# oled_control.net
KiCad netlist of a schematic drawn in Altium Designer
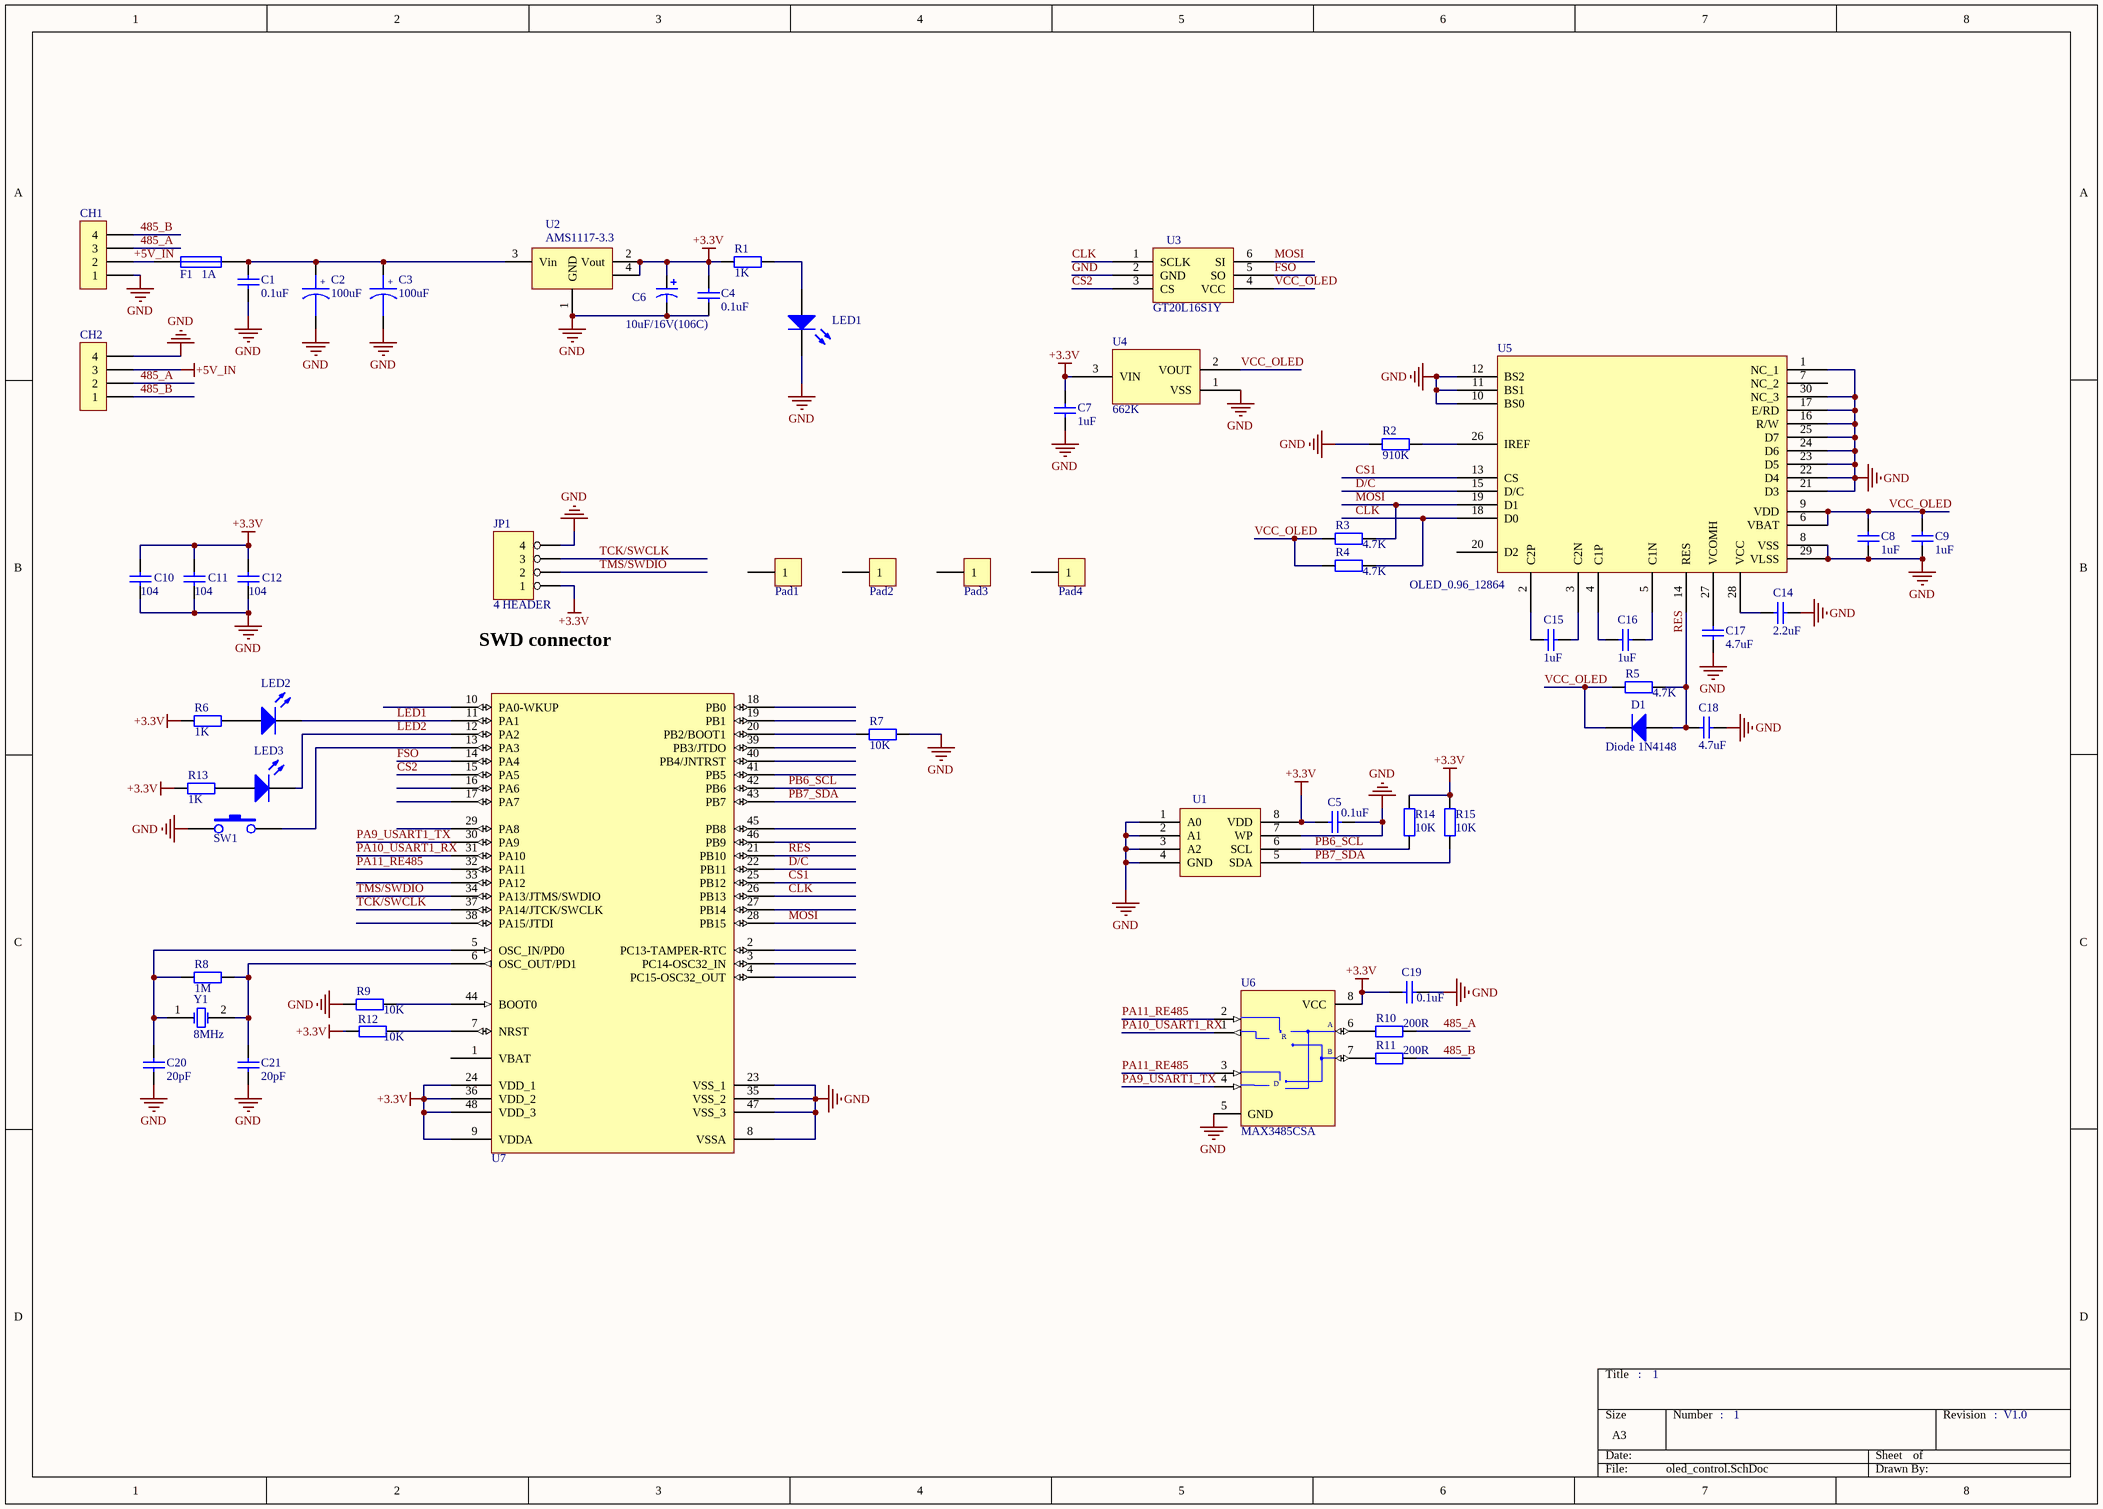
[diagram p0: oled_control.SchDoc]

(export (version "E")
  (design (tool "Eeschema 10.0.6"))
  (components
    (comp (ref "C1")
      (value "0.1uF")
      (footprint "0805")
      (description "Capacitor")
      (fields (field (name "Comment") "Cap") (field (name "PUBLISHER") "Altium Limited"))
      (libsource (lib "Miscellaneous Devices") (part "Cap"))
    )
    (comp (ref "C2")
      (value "C_2200uF")
      (footprint "B: 3528")
      (fields (field (name "ALTIUM_UNNAMED_1") "100uF"))
      (libsource (lib "myIntegrated_Library1") (part "C_2200uF"))
    )
    (comp (ref "C3")
      (value "C_2200uF")
      (footprint "B: 3528")
      (fields (field (name "ALTIUM_UNNAMED_1") "100uF"))
      (libsource (lib "myIntegrated_Library1") (part "C_2200uF"))
    )
    (comp (ref "C4")
      (value "0.1uF")
      (footprint "0805")
      (description "Capacitor")
      (fields (field (name "Comment") "Cap") (field (name "PUBLISHER") "Altium Limited"))
      (libsource (lib "Miscellaneous Devices") (part "Cap"))
    )
    (comp (ref "C5")
      (value "0.1uF")
      (footprint "0805")
      (description "Capacitor")
      (fields (field (name "Comment") "Cap") (field (name "PUBLISHER") "Altium Limited"))
      (libsource (lib "Miscellaneous Devices") (part "Cap"))
    )
    (comp (ref "C6")
      (value "10uF/16V(106C)")
      (footprint "CAP A-3216")
      (description "Polarized Capacitor (Surface Mount)")
      (fields (field (name "Comment") "Cap Pol3") (field (name "PUBLISHER") "Altium Limited"))
      (libsource (lib "Miscellaneous Devices") (part "Cap Pol3"))
    )
    (comp (ref "C7")
      (value "1uF")
      (footprint "0805")
      (description "Capacitor")
      (fields (field (name "Comment") "Cap") (field (name "PUBLISHER") "Altium Limited"))
      (libsource (lib "Miscellaneous Devices") (part "Cap"))
    )
    (comp (ref "C8")
      (value "1uF")
      (footprint "0805")
      (description "Capacitor")
      (fields (field (name "Comment") "Cap") (field (name "PUBLISHER") "Altium Limited"))
      (libsource (lib "Miscellaneous Devices") (part "Cap"))
    )
    (comp (ref "C9")
      (value "1uF")
      (footprint "0805")
      (description "Capacitor")
      (fields (field (name "Comment") "Cap") (field (name "PUBLISHER") "Altium Limited"))
      (libsource (lib "Miscellaneous Devices") (part "Cap"))
    )
    (comp (ref "C10")
      (value "104")
      (footprint "0805")
      (description "Capacitor")
      (fields (field (name "Comment") "Cap") (field (name "PUBLISHER") "Altium Limited"))
      (libsource (lib "Miscellaneous Devices") (part "Cap"))
    )
    (comp (ref "C11")
      (value "104")
      (footprint "0805")
      (description "Capacitor")
      (fields (field (name "Comment") "Cap") (field (name "PUBLISHER") "Altium Limited"))
      (libsource (lib "Miscellaneous Devices") (part "Cap"))
    )
    (comp (ref "C12")
      (value "104")
      (footprint "0805")
      (description "Capacitor")
      (fields (field (name "Comment") "Cap") (field (name "PUBLISHER") "Altium Limited"))
      (libsource (lib "Miscellaneous Devices") (part "Cap"))
    )
    (comp (ref "C14")
      (value "2.2uF")
      (footprint "0805")
      (description "Capacitor")
      (fields (field (name "Comment") "Cap") (field (name "PUBLISHER") "Altium Limited"))
      (libsource (lib "Miscellaneous Devices") (part "Cap"))
    )
    (comp (ref "C15")
      (value "1uF")
      (footprint "0805")
      (description "Capacitor")
      (fields (field (name "Comment") "Cap") (field (name "PUBLISHER") "Altium Limited"))
      (libsource (lib "Miscellaneous Devices") (part "Cap"))
    )
    (comp (ref "C16")
      (value "1uF")
      (footprint "0805")
      (description "Capacitor")
      (fields (field (name "Comment") "Cap") (field (name "PUBLISHER") "Altium Limited"))
      (libsource (lib "Miscellaneous Devices") (part "Cap"))
    )
    (comp (ref "C17")
      (value "4.7uF")
      (footprint "0805")
      (description "Capacitor")
      (fields (field (name "Comment") "Cap") (field (name "PUBLISHER") "Altium Limited"))
      (libsource (lib "Miscellaneous Devices") (part "Cap"))
    )
    (comp (ref "C18")
      (value "4.7uF")
      (footprint "0805")
      (description "Capacitor")
      (fields (field (name "Comment") "Cap") (field (name "PUBLISHER") "Altium Limited"))
      (libsource (lib "Miscellaneous Devices") (part "Cap"))
    )
    (comp (ref "C19")
      (value "0.1uF")
      (footprint "0805")
      (description "Capacitor")
      (fields (field (name "Comment") "Cap") (field (name "PUBLISHER") "Altium Limited"))
      (libsource (lib "Miscellaneous Devices") (part "Cap"))
    )
    (comp (ref "C20")
      (value "20pF")
      (footprint "0805")
      (description "Capacitor")
      (fields (field (name "Comment") "Cap") (field (name "PUBLISHER") "Altium Limited"))
      (libsource (lib "开发板元件库") (part "Cap"))
    )
    (comp (ref "C21")
      (value "20pF")
      (footprint "0805")
      (description "Capacitor")
      (fields (field (name "Comment") "Cap") (field (name "PUBLISHER") "Altium Limited"))
      (libsource (lib "开发板元件库") (part "Cap"))
    )
    (comp (ref "CH1")
      (value "HEADER1X4")
      (footprint "CON4_1.5")
      (libsource (lib "myIntegrated_Library1") (part "HEADER1X4"))
    )
    (comp (ref "CH2")
      (value "HEADER1X4")
      (footprint "CON4_1.5")
      (libsource (lib "myIntegrated_Library1") (part "HEADER1X4"))
    )
    (comp (ref "D1")
      (value "Diode 1N4148")
      (footprint "LL34")
      (description "High Conductance Fast Diode")
      (fields (field (name "PUBLISHER") "Altium Limited"))
      (libsource (lib "Miscellaneous Devices") (part "Diode 1N4148"))
    )
    (comp (ref "F1")
      (value "FUSE")
      (footprint "0805")
      (fields (field (name "ALTIUM_UNNAMED_1") "1A"))
      (libsource (lib "myIntegrated_Library1") (part "FUSE"))
    )
    (comp (ref "JP1")
      (value "4 HEADER")
      (footprint "CON4_1.5")
      (description "4 Pin Header")
      (libsource (lib "Miscellaneous Devices") (part "4 HEADER"))
    )
    (comp (ref "LED1")
      (value "~")
      (footprint "LED-0805")
      (description "Typical RED, GREEN, YELLOW, AMBER GaAs LED")
      (fields (field (name "PUBLISHER") "Altium Limited"))
      (libsource (lib "Miscellaneous Devices") (part "LED2"))
    )
    (comp (ref "LED2")
      (value "~")
      (footprint "LED-0805")
      (description "Typical RED, GREEN, YELLOW, AMBER GaAs LED")
      (fields (field (name "PUBLISHER") "Altium Limited"))
      (libsource (lib "Miscellaneous Devices") (part "LED2"))
    )
    (comp (ref "LED3")
      (value "~")
      (footprint "LED_5X5")
      (description "Typical RED, GREEN, YELLOW, AMBER GaAs LED")
      (fields (field (name "PUBLISHER") "Altium Limited"))
      (libsource (lib "Miscellaneous Devices") (part "LED2"))
    )
    (comp (ref "Pad1")
      (value "Pad")
      (footprint "pad35")
      (libsource (lib "myIntegrated_Library1") (part "Pad"))
    )
    (comp (ref "Pad2")
      (value "Pad")
      (footprint "pad35")
      (libsource (lib "myIntegrated_Library1") (part "Pad"))
    )
    (comp (ref "Pad3")
      (value "Pad")
      (footprint "pad35")
      (libsource (lib "myIntegrated_Library1") (part "Pad"))
    )
    (comp (ref "Pad4")
      (value "Pad")
      (footprint "pad35")
      (libsource (lib "myIntegrated_Library1") (part "Pad"))
    )
    (comp (ref "R1")
      (value "1K")
      (footprint "0805")
      (description "Resistor")
      (fields (field (name "Comment") "Res2") (field (name "PUBLISHER") "Altium Limited"))
      (libsource (lib "Miscellaneous Devices") (part "Res2"))
    )
    (comp (ref "R2")
      (value "910K")
      (footprint "0805")
      (description "Resistor")
      (fields (field (name "Comment") "Res2") (field (name "PUBLISHER") "Altium Limited"))
      (libsource (lib "Miscellaneous Devices") (part "Res2"))
    )
    (comp (ref "R3")
      (value "4.7K")
      (footprint "0805")
      (description "Resistor")
      (fields (field (name "Comment") "Res2") (field (name "PUBLISHER") "Altium Limited"))
      (libsource (lib "Miscellaneous Devices") (part "Res2"))
    )
    (comp (ref "R4")
      (value "4.7K")
      (footprint "0805")
      (description "Resistor")
      (fields (field (name "Comment") "Res2") (field (name "PUBLISHER") "Altium Limited"))
      (libsource (lib "Miscellaneous Devices") (part "Res2"))
    )
    (comp (ref "R5")
      (value "4.7K")
      (footprint "0805")
      (description "Resistor")
      (fields (field (name "Comment") "Res2") (field (name "PUBLISHER") "Altium Limited"))
      (libsource (lib "Miscellaneous Devices") (part "Res2"))
    )
    (comp (ref "R6")
      (value "1K")
      (footprint "0805")
      (description "Resistor")
      (fields (field (name "Comment") "Res2") (field (name "PUBLISHER") "Altium Limited"))
      (libsource (lib "Miscellaneous Devices") (part "Res2"))
    )
    (comp (ref "R7")
      (value "10K")
      (footprint "0805")
      (description "Resistor")
      (fields (field (name "Comment") "Res2") (field (name "PUBLISHER") "Altium Limited"))
      (libsource (lib "开发板元件库") (part "Res2"))
    )
    (comp (ref "R8")
      (value "1M")
      (footprint "0805")
      (description "Resistor")
      (fields (field (name "Comment") "Res2") (field (name "PUBLISHER") "Altium Limited"))
      (libsource (lib "开发板元件库") (part "Res2"))
    )
    (comp (ref "R9")
      (value "10K")
      (footprint "0805")
      (description "Resistor")
      (fields (field (name "Comment") "Res2") (field (name "PUBLISHER") "Altium Limited"))
      (libsource (lib "开发板元件库") (part "Res2"))
    )
    (comp (ref "R10")
      (value "200R")
      (footprint "0805")
      (description "Resistor")
      (fields (field (name "Comment") "Res2") (field (name "PUBLISHER") "Altium Limited"))
      (libsource (lib "") (part "Res2_2"))
    )
    (comp (ref "R11")
      (value "200R")
      (footprint "0805")
      (description "Resistor")
      (fields (field (name "Comment") "Res2") (field (name "PUBLISHER") "Altium Limited"))
      (libsource (lib "") (part "Res2_2"))
    )
    (comp (ref "R12")
      (value "10K")
      (footprint "0805")
      (description "Resistor")
      (fields (field (name "Comment") "Res2") (field (name "PUBLISHER") "Altium Limited"))
      (libsource (lib "开发板元件库") (part "Res2"))
    )
    (comp (ref "R13")
      (value "1K")
      (footprint "0805")
      (description "Resistor")
      (fields (field (name "Comment") "Res2") (field (name "PUBLISHER") "Altium Limited"))
      (libsource (lib "Miscellaneous Devices") (part "Res2"))
    )
    (comp (ref "R14")
      (value "10K")
      (footprint "C0805tan")
      (description "Resistor")
      (fields (field (name "Comment") "Res2") (field (name "PUBLISHER") "Altium Limited"))
      (libsource (lib "") (part "Res2_1"))
    )
    (comp (ref "R15")
      (value "10K")
      (footprint "C0805tan")
      (description "Resistor")
      (fields (field (name "Comment") "Res2") (field (name "PUBLISHER") "Altium Limited"))
      (libsource (lib "") (part "Res2_1"))
    )
    (comp (ref "SW1")
      (value "SW-KEY-2")
      (footprint "KEY_SOP4")
      (libsource (lib "myIntegrated_Library1") (part "SW-KEY-2"))
    )
    (comp (ref "U1")
      (value "AT24c02")
      (footprint "TSSOP8")
      (libsource (lib "myIntegrated_Library1") (part "TI24c02"))
    )
    (comp (ref "U2")
      (value "AMS1117-3.3")
      (footprint "SOT223")
      (libsource (lib "货架电子标签元件库") (part "AMS1117-5"))
    )
    (comp (ref "U3")
      (value "GT20L16S1Y")
      (footprint "SOT23-6")
      (libsource (lib "myIntegrated_Library1") (part "GT20L16S1Y"))
    )
    (comp (ref "U4")
      (value "662K")
      (footprint "SOT-23")
      (libsource (lib "myIntegrated_Library1") (part "662K"))
    )
    (comp (ref "U5")
      (value "OLED_0.96_12864")
      (footprint "OLED_1.30_12864")
      (libsource (lib "myIntegrated_Library1") (part "OLED_0.96_12864"))
    )
    (comp (ref "U6")
      (value "MAX3485CSA")
      (footprint "NS08-L")
      (libsource (lib "myIntegrated_Library1") (part "MAX485CSA"))
    )
    (comp (ref "U7")
      (value "STM32F103C8T6")
      (footprint "LQFP48")
      (libsource (lib "myIntegrated_Library1") (part "STM32F103C8T6"))
    )
    (comp (ref "Y1")
      (value "8MHz")
      (footprint "XTAL_US1")
      (description "Crystal Oscillator")
      (fields (field (name "PUBLISHER") "Altium Limited"))
      (libsource (lib "战舰STM32开发板底板封装库") (part "XTAL"))
    )
  )
  (nets
    (net (code "1") (name "+3.3V") (class "Default")
      (node (ref "C10") (pin "2") (pinfunction "2_2") (pintype "passive"))
      (node (ref "C11") (pin "2") (pinfunction "2_2") (pintype "passive"))
      (node (ref "C12") (pin "2") (pinfunction "2_2") (pintype "passive"))
      (node (ref "C19") (pin "1") (pinfunction "1_1") (pintype "passive"))
      (node (ref "C4") (pin "2") (pinfunction "2_2") (pintype "passive"))
      (node (ref "C5") (pin "2") (pinfunction "2_2") (pintype "passive"))
      (node (ref "C6") (pin "1") (pinfunction "1_1") (pintype "passive"))
      (node (ref "C7") (pin "1") (pinfunction "1_1") (pintype "passive"))
      (node (ref "JP1") (pin "1") (pinfunction "1_1") (pintype "passive"))
      (node (ref "R1") (pin "2") (pinfunction "2_2") (pintype "passive"))
      (node (ref "R12") (pin "1") (pinfunction "1_1") (pintype "passive"))
      (node (ref "R13") (pin "2") (pinfunction "2_2") (pintype "passive"))
      (node (ref "R14") (pin "2") (pinfunction "2_2") (pintype "passive"))
      (node (ref "R15") (pin "2") (pinfunction "2_2") (pintype "passive"))
      (node (ref "R6") (pin "2") (pinfunction "2_2") (pintype "passive"))
      (node (ref "U1") (pin "8") (pinfunction "VDD_8") (pintype "passive"))
      (node (ref "U2") (pin "2") (pinfunction "Vout_2") (pintype "passive"))
      (node (ref "U2") (pin "4") (pintype "passive"))
      (node (ref "U4") (pin "3") (pinfunction "VIN_3") (pintype "passive"))
      (node (ref "U6") (pin "8") (pinfunction "VCC_8") (pintype "power_in"))
      (node (ref "U7") (pin "24") (pinfunction "VDD_1_24") (pintype "power_in"))
      (node (ref "U7") (pin "36") (pinfunction "VDD_2_36") (pintype "power_in"))
      (node (ref "U7") (pin "48") (pinfunction "VDD_3_48") (pintype "power_in"))
      (node (ref "U7") (pin "9") (pinfunction "VDDA_9") (pintype "power_in"))
    )
    (net (code "2") (name "+5V_IN") (class "Default")
      (node (ref "CH1") (pin "2") (pinfunction "2_2") (pintype "passive"))
      (node (ref "CH2") (pin "3") (pinfunction "3_3") (pintype "passive"))
      (node (ref "F1") (pin "1") (pinfunction "1_1") (pintype "passive"))
    )
    (net (code "3") (name "/485_A") (class "Default")
      (node (ref "CH1") (pin "3") (pinfunction "3_3") (pintype "passive"))
      (node (ref "CH2") (pin "2") (pinfunction "2_2") (pintype "passive"))
      (node (ref "R10") (pin "2") (pinfunction "2_2") (pintype "passive"))
    )
    (net (code "4") (name "/485_B") (class "Default")
      (node (ref "CH1") (pin "4") (pinfunction "4_4") (pintype "passive"))
      (node (ref "CH2") (pin "1") (pinfunction "1_1") (pintype "passive"))
      (node (ref "R11") (pin "2") (pinfunction "2_2") (pintype "passive"))
    )
    (net (code "5") (name "/CLK") (class "Default")
      (node (ref "R4") (pin "1") (pinfunction "1_1") (pintype "passive"))
      (node (ref "U3") (pin "1") (pinfunction "SCLK_1") (pintype "passive"))
      (node (ref "U5") (pin "18") (pinfunction "D0_18") (pintype "passive"))
      (node (ref "U7") (pin "26") (pinfunction "PB13_26") (pintype "bidirectional"))
    )
    (net (code "6") (name "/CS1") (class "Default")
      (node (ref "U5") (pin "13") (pinfunction "CS_13") (pintype "passive"))
      (node (ref "U7") (pin "25") (pinfunction "PB12_25") (pintype "bidirectional"))
    )
    (net (code "7") (name "/CS2") (class "Default")
      (node (ref "U3") (pin "3") (pinfunction "CS_3") (pintype "passive"))
      (node (ref "U7") (pin "15") (pinfunction "PA5_15") (pintype "bidirectional"))
    )
    (net (code "8") (name "/D{slash}C") (class "Default")
      (node (ref "U5") (pin "15") (pinfunction "D/C_15") (pintype "passive"))
      (node (ref "U7") (pin "22") (pinfunction "PB11_22") (pintype "bidirectional"))
    )
    (net (code "9") (name "/FSO") (class "Default")
      (node (ref "U3") (pin "5") (pinfunction "SO_5") (pintype "passive"))
      (node (ref "U7") (pin "14") (pinfunction "PA4_14") (pintype "bidirectional"))
    )
    (net (code "10") (name "/LED1") (class "Default")
      (node (ref "LED2") (pin "2") (pinfunction "K_2") (pintype "passive"))
      (node (ref "U7") (pin "11") (pinfunction "PA1_11") (pintype "bidirectional"))
    )
    (net (code "11") (name "/LED2") (class "Default")
      (node (ref "LED3") (pin "2") (pinfunction "K_2") (pintype "passive"))
      (node (ref "U7") (pin "12") (pinfunction "PA2_12") (pintype "bidirectional"))
    )
    (net (code "12") (name "/MOSI") (class "Default")
      (node (ref "R3") (pin "1") (pinfunction "1_1") (pintype "passive"))
      (node (ref "U3") (pin "6") (pinfunction "SI_6") (pintype "passive"))
      (node (ref "U5") (pin "19") (pinfunction "D1_19") (pintype "passive"))
      (node (ref "U7") (pin "28") (pinfunction "PB15_28") (pintype "bidirectional"))
    )
    (net (code "13") (name "/PA9_USART1_TX") (class "Default")
      (node (ref "U6") (pin "4") (pinfunction "DI_4") (pintype "input"))
      (node (ref "U7") (pin "30") (pinfunction "PA9_30") (pintype "bidirectional"))
    )
    (net (code "14") (name "/PA10_USART1_RX") (class "Default")
      (node (ref "U6") (pin "1") (pinfunction "RO_1") (pintype "output"))
      (node (ref "U7") (pin "31") (pinfunction "PA10_31") (pintype "bidirectional"))
    )
    (net (code "15") (name "/PA11_RE485") (class "Default")
      (node (ref "U6") (pin "2") (pinfunction "~{RE}_2") (pintype "input"))
      (node (ref "U6") (pin "3") (pinfunction "DE_3") (pintype "input"))
      (node (ref "U7") (pin "32") (pinfunction "PA11_32") (pintype "bidirectional"))
    )
    (net (code "16") (name "/PB6_SCL") (class "Default")
      (node (ref "R14") (pin "1") (pinfunction "1_1") (pintype "passive"))
      (node (ref "U1") (pin "6") (pinfunction "SCL_6") (pintype "passive"))
      (node (ref "U7") (pin "42") (pinfunction "PB6_42") (pintype "bidirectional"))
    )
    (net (code "17") (name "/PB7_SDA") (class "Default")
      (node (ref "R15") (pin "1") (pinfunction "1_1") (pintype "passive"))
      (node (ref "U1") (pin "5") (pinfunction "SDA_5") (pintype "passive"))
      (node (ref "U7") (pin "43") (pinfunction "PB7_43") (pintype "bidirectional"))
    )
    (net (code "18") (name "/RES") (class "Default")
      (node (ref "C18") (pin "2") (pinfunction "2_2") (pintype "passive"))
      (node (ref "D1") (pin "1") (pinfunction "A_1") (pintype "passive"))
      (node (ref "R5") (pin "1") (pinfunction "1_1") (pintype "passive"))
      (node (ref "U5") (pin "14") (pinfunction "RES_14") (pintype "passive"))
      (node (ref "U7") (pin "21") (pinfunction "PB10_21") (pintype "bidirectional"))
    )
    (net (code "19") (name "/TCK{slash}SWCLK") (class "Default")
      (node (ref "JP1") (pin "3") (pinfunction "3_3") (pintype "passive"))
      (node (ref "U7") (pin "37") (pinfunction "PA14/JTCK/SWCLK_37") (pintype "bidirectional"))
    )
    (net (code "20") (name "/TMS{slash}SWDIO") (class "Default")
      (node (ref "JP1") (pin "2") (pinfunction "2_2") (pintype "passive"))
      (node (ref "U7") (pin "34") (pinfunction "PA13/JTMS/SWDIO_34") (pintype "bidirectional"))
    )
    (net (code "21") (name "/VCC_OLED") (class "Default")
      (node (ref "C8") (pin "1") (pinfunction "1_1") (pintype "passive"))
      (node (ref "C9") (pin "1") (pinfunction "1_1") (pintype "passive"))
      (node (ref "D1") (pin "2") (pinfunction "K_2") (pintype "passive"))
      (node (ref "R3") (pin "2") (pinfunction "2_2") (pintype "passive"))
      (node (ref "R4") (pin "2") (pinfunction "2_2") (pintype "passive"))
      (node (ref "R5") (pin "2") (pinfunction "2_2") (pintype "passive"))
      (node (ref "U3") (pin "4") (pinfunction "VCC_4") (pintype "passive"))
      (node (ref "U4") (pin "2") (pinfunction "VOUT_2") (pintype "passive"))
      (node (ref "U5") (pin "6") (pinfunction "VBAT_6") (pintype "passive"))
      (node (ref "U5") (pin "9") (pinfunction "VDD_9") (pintype "passive"))
    )
    (net (code "22") (name "GND") (class "Default")
      (node (ref "C1") (pin "1") (pinfunction "1_1") (pintype "passive"))
      (node (ref "C10") (pin "1") (pinfunction "1_1") (pintype "passive"))
      (node (ref "C11") (pin "1") (pinfunction "1_1") (pintype "passive"))
      (node (ref "C12") (pin "1") (pinfunction "1_1") (pintype "passive"))
      (node (ref "C14") (pin "1") (pinfunction "1_1") (pintype "passive"))
      (node (ref "C17") (pin "2") (pinfunction "2_2") (pintype "passive"))
      (node (ref "C18") (pin "1") (pinfunction "1_1") (pintype "passive"))
      (node (ref "C19") (pin "2") (pinfunction "2_2") (pintype "passive"))
      (node (ref "C2") (pin "2") (pinfunction "2_2") (pintype "passive"))
      (node (ref "C20") (pin "1") (pinfunction "1_1") (pintype "passive"))
      (node (ref "C21") (pin "1") (pinfunction "1_1") (pintype "passive"))
      (node (ref "C3") (pin "2") (pinfunction "2_2") (pintype "passive"))
      (node (ref "C4") (pin "1") (pinfunction "1_1") (pintype "passive"))
      (node (ref "C5") (pin "1") (pinfunction "1_1") (pintype "passive"))
      (node (ref "C6") (pin "2") (pinfunction "2_2") (pintype "passive"))
      (node (ref "C7") (pin "2") (pinfunction "2_2") (pintype "passive"))
      (node (ref "C8") (pin "2") (pinfunction "2_2") (pintype "passive"))
      (node (ref "C9") (pin "2") (pinfunction "2_2") (pintype "passive"))
      (node (ref "CH1") (pin "1") (pinfunction "1_1") (pintype "passive"))
      (node (ref "CH2") (pin "4") (pinfunction "4_4") (pintype "passive"))
      (node (ref "JP1") (pin "4") (pinfunction "4_4") (pintype "passive"))
      (node (ref "LED1") (pin "2") (pinfunction "K_2") (pintype "passive"))
      (node (ref "R2") (pin "2") (pinfunction "2_2") (pintype "passive"))
      (node (ref "R7") (pin "2") (pinfunction "2_2") (pintype "passive"))
      (node (ref "R9") (pin "1") (pinfunction "1_1") (pintype "passive"))
      (node (ref "SW1") (pin "1") (pinfunction "1_1") (pintype "passive"))
      (node (ref "U1") (pin "1") (pinfunction "A0_1") (pintype "passive"))
      (node (ref "U1") (pin "2") (pinfunction "A1_2") (pintype "passive"))
      (node (ref "U1") (pin "3") (pinfunction "A2_3") (pintype "passive"))
      (node (ref "U1") (pin "4") (pinfunction "GND_4") (pintype "passive"))
      (node (ref "U1") (pin "7") (pinfunction "WP_7") (pintype "passive"))
      (node (ref "U2") (pin "1") (pinfunction "GND_1") (pintype "passive"))
      (node (ref "U3") (pin "2") (pinfunction "GND_2") (pintype "passive"))
      (node (ref "U4") (pin "1") (pinfunction "VSS_1") (pintype "passive"))
      (node (ref "U5") (pin "1") (pinfunction "NC_1_1") (pintype "passive"))
      (node (ref "U5") (pin "10") (pinfunction "BS0_10") (pintype "passive"))
      (node (ref "U5") (pin "11") (pinfunction "BS1_11") (pintype "passive"))
      (node (ref "U5") (pin "12") (pinfunction "BS2_12") (pintype "passive"))
      (node (ref "U5") (pin "16") (pinfunction "R/W_16") (pintype "passive"))
      (node (ref "U5") (pin "17") (pinfunction "E/RD_17") (pintype "passive"))
      (node (ref "U5") (pin "21") (pinfunction "D3_21") (pintype "passive"))
      (node (ref "U5") (pin "22") (pinfunction "D4_22") (pintype "passive"))
      (node (ref "U5") (pin "23") (pinfunction "D5_23") (pintype "passive"))
      (node (ref "U5") (pin "24") (pinfunction "D6_24") (pintype "passive"))
      (node (ref "U5") (pin "25") (pinfunction "D7_25") (pintype "passive"))
      (node (ref "U5") (pin "29") (pinfunction "VLSS_29") (pintype "passive"))
      (node (ref "U5") (pin "30") (pinfunction "NC_3_30") (pintype "passive"))
      (node (ref "U5") (pin "8") (pinfunction "VSS_8") (pintype "passive"))
      (node (ref "U6") (pin "5") (pinfunction "GND_5") (pintype "power_in"))
      (node (ref "U7") (pin "23") (pinfunction "VSS_1_23") (pintype "power_in"))
      (node (ref "U7") (pin "35") (pinfunction "VSS_2_35") (pintype "power_in"))
      (node (ref "U7") (pin "47") (pinfunction "VSS_3_47") (pintype "power_in"))
      (node (ref "U7") (pin "8") (pinfunction "VSSA_8") (pintype "power_in"))
    )
    (net (code "23") (name "Net-(LED1-A)") (class "Default")
      (node (ref "LED1") (pin "1") (pinfunction "A_1") (pintype "passive"))
      (node (ref "R1") (pin "1") (pinfunction "1_1") (pintype "passive"))
    )
    (net (code "24") (name "Net-(LED2-A)") (class "Default")
      (node (ref "LED2") (pin "1") (pinfunction "A_1") (pintype "passive"))
      (node (ref "R6") (pin "1") (pinfunction "1_1") (pintype "passive"))
    )
    (net (code "25") (name "Net-(LED3-A)") (class "Default")
      (node (ref "LED3") (pin "1") (pinfunction "A_1") (pintype "passive"))
      (node (ref "R13") (pin "1") (pinfunction "1_1") (pintype "passive"))
    )
    (net (code "26") (name "Net-(U2-Vin)") (class "Default")
      (node (ref "C1") (pin "2") (pinfunction "2_2") (pintype "passive"))
      (node (ref "C2") (pin "1") (pinfunction "1_1") (pintype "passive"))
      (node (ref "C3") (pin "1") (pinfunction "1_1") (pintype "passive"))
      (node (ref "F1") (pin "2") (pinfunction "2_2") (pintype "passive"))
      (node (ref "U2") (pin "3") (pinfunction "Vin_3") (pintype "passive"))
    )
    (net (code "27") (name "Net-(U5-C1N)") (class "Default")
      (node (ref "C16") (pin "1") (pinfunction "1_1") (pintype "passive"))
      (node (ref "U5") (pin "5") (pinfunction "C1N_5") (pintype "passive"))
    )
    (net (code "28") (name "Net-(U5-C1P)") (class "Default")
      (node (ref "C16") (pin "2") (pinfunction "2_2") (pintype "passive"))
      (node (ref "U5") (pin "4") (pinfunction "C1P_4") (pintype "passive"))
    )
    (net (code "29") (name "Net-(U5-C2N)") (class "Default")
      (node (ref "C15") (pin "1") (pinfunction "1_1") (pintype "passive"))
      (node (ref "U5") (pin "3") (pinfunction "C2N_3") (pintype "passive"))
    )
    (net (code "30") (name "Net-(U5-C2P)") (class "Default")
      (node (ref "C15") (pin "2") (pinfunction "2_2") (pintype "passive"))
      (node (ref "U5") (pin "2") (pinfunction "C2P_2") (pintype "passive"))
    )
    (net (code "31") (name "Net-(U5-IREF)") (class "Default")
      (node (ref "R2") (pin "1") (pinfunction "1_1") (pintype "passive"))
      (node (ref "U5") (pin "26") (pinfunction "IREF_26") (pintype "passive"))
    )
    (net (code "32") (name "Net-(U5-VCC)") (class "Default")
      (node (ref "C14") (pin "2") (pinfunction "2_2") (pintype "passive"))
      (node (ref "U5") (pin "28") (pinfunction "VCC_28") (pintype "passive"))
    )
    (net (code "33") (name "Net-(U5-VCOMH)") (class "Default")
      (node (ref "C17") (pin "1") (pinfunction "1_1") (pintype "passive"))
      (node (ref "U5") (pin "27") (pinfunction "VCOMH_27") (pintype "passive"))
    )
    (net (code "34") (name "Net-(U6-A)") (class "Default")
      (node (ref "R10") (pin "1") (pinfunction "1_1") (pintype "passive"))
      (node (ref "U6") (pin "6") (pinfunction "A_6") (pintype "bidirectional"))
    )
    (net (code "35") (name "Net-(U6-B)") (class "Default")
      (node (ref "R11") (pin "1") (pinfunction "1_1") (pintype "passive"))
      (node (ref "U6") (pin "7") (pinfunction "B_7") (pintype "bidirectional"))
    )
    (net (code "36") (name "Net-(U7-BOOT0)") (class "Default")
      (node (ref "R9") (pin "2") (pinfunction "2_2") (pintype "passive"))
      (node (ref "U7") (pin "44") (pinfunction "BOOT0_44") (pintype "input"))
    )
    (net (code "37") (name "Net-(U7-NRST)") (class "Default")
      (node (ref "R12") (pin "2") (pinfunction "2_2") (pintype "passive"))
      (node (ref "U7") (pin "7") (pinfunction "NRST_7") (pintype "bidirectional"))
    )
    (net (code "38") (name "Net-(U7-OSC_IN{slash}PD0)") (class "Default")
      (node (ref "C20") (pin "2") (pinfunction "2_2") (pintype "passive"))
      (node (ref "R8") (pin "1") (pinfunction "1_1") (pintype "passive"))
      (node (ref "U7") (pin "5") (pinfunction "OSC_IN/PD0_5") (pintype "input"))
      (node (ref "Y1") (pin "1") (pinfunction "OSC1_1") (pintype "passive"))
    )
    (net (code "39") (name "Net-(U7-OSC_OUT{slash}PD1)") (class "Default")
      (node (ref "C21") (pin "2") (pinfunction "2_2") (pintype "passive"))
      (node (ref "R8") (pin "2") (pinfunction "2_2") (pintype "passive"))
      (node (ref "U7") (pin "6") (pinfunction "OSC_OUT/PD1_6") (pintype "output"))
      (node (ref "Y1") (pin "2") (pinfunction "OSC2_2") (pintype "passive"))
    )
    (net (code "40") (name "Net-(U7-PA3)") (class "Default")
      (node (ref "SW1") (pin "2") (pinfunction "2_2") (pintype "passive"))
      (node (ref "U7") (pin "13") (pinfunction "PA3_13") (pintype "bidirectional"))
    )
    (net (code "41") (name "Net-(U7-PB2{slash}BOOT1)") (class "Default")
      (node (ref "R7") (pin "1") (pinfunction "1_1") (pintype "passive"))
      (node (ref "U7") (pin "20") (pinfunction "PB2/BOOT1_20") (pintype "bidirectional"))
    )
    (net (code "42") (name "unconnected-(Pad1-Pad1)") (class "Default")
      (node (ref "Pad1") (pin "1") (pinfunction "1_1") (pintype "passive"))
    )
    (net (code "43") (name "unconnected-(Pad2-Pad1)") (class "Default")
      (node (ref "Pad2") (pin "1") (pinfunction "1_1") (pintype "passive"))
    )
    (net (code "44") (name "unconnected-(Pad3-Pad1)") (class "Default")
      (node (ref "Pad3") (pin "1") (pinfunction "1_1") (pintype "passive"))
    )
    (net (code "45") (name "unconnected-(Pad4-Pad1)") (class "Default")
      (node (ref "Pad4") (pin "1") (pinfunction "1_1") (pintype "passive"))
    )
    (net (code "46") (name "unconnected-(U5-D2-Pad20)") (class "Default")
      (node (ref "U5") (pin "20") (pinfunction "D2_20") (pintype "passive"))
    )
    (net (code "47") (name "unconnected-(U5-NC_2-Pad7)") (class "Default")
      (node (ref "U5") (pin "7") (pinfunction "NC_2_7") (pintype "passive"))
    )
    (net (code "48") (name "unconnected-(U7-PA0-WKUP-Pad10)") (class "Default")
      (node (ref "U7") (pin "10") (pinfunction "PA0-WKUP_10") (pintype "bidirectional"))
    )
    (net (code "49") (name "unconnected-(U7-PA6-Pad16)") (class "Default")
      (node (ref "U7") (pin "16") (pinfunction "PA6_16") (pintype "bidirectional"))
    )
    (net (code "50") (name "unconnected-(U7-PA7-Pad17)") (class "Default")
      (node (ref "U7") (pin "17") (pinfunction "PA7_17") (pintype "bidirectional"))
    )
    (net (code "51") (name "unconnected-(U7-PA8-Pad29)") (class "Default")
      (node (ref "U7") (pin "29") (pinfunction "PA8_29") (pintype "bidirectional"))
    )
    (net (code "52") (name "unconnected-(U7-PA12-Pad33)") (class "Default")
      (node (ref "U7") (pin "33") (pinfunction "PA12_33") (pintype "bidirectional"))
    )
    (net (code "53") (name "unconnected-(U7-PA15{slash}JTDI-Pad38)") (class "Default")
      (node (ref "U7") (pin "38") (pinfunction "PA15/JTDI_38") (pintype "bidirectional"))
    )
    (net (code "54") (name "unconnected-(U7-PB0-Pad18)") (class "Default")
      (node (ref "U7") (pin "18") (pinfunction "PB0_18") (pintype "bidirectional"))
    )
    (net (code "55") (name "unconnected-(U7-PB1-Pad19)") (class "Default")
      (node (ref "U7") (pin "19") (pinfunction "PB1_19") (pintype "bidirectional"))
    )
    (net (code "56") (name "unconnected-(U7-PB3{slash}JTDO-Pad39)") (class "Default")
      (node (ref "U7") (pin "39") (pinfunction "PB3/JTDO_39") (pintype "bidirectional"))
    )
    (net (code "57") (name "unconnected-(U7-PB4{slash}JNTRST-Pad40)") (class "Default")
      (node (ref "U7") (pin "40") (pinfunction "PB4/JNTRST_40") (pintype "bidirectional"))
    )
    (net (code "58") (name "unconnected-(U7-PB5-Pad41)") (class "Default")
      (node (ref "U7") (pin "41") (pinfunction "PB5_41") (pintype "bidirectional"))
    )
    (net (code "59") (name "unconnected-(U7-PB8-Pad45)") (class "Default")
      (node (ref "U7") (pin "45") (pinfunction "PB8_45") (pintype "bidirectional"))
    )
    (net (code "60") (name "unconnected-(U7-PB9-Pad46)") (class "Default")
      (node (ref "U7") (pin "46") (pinfunction "PB9_46") (pintype "bidirectional"))
    )
    (net (code "61") (name "unconnected-(U7-PB14-Pad27)") (class "Default")
      (node (ref "U7") (pin "27") (pinfunction "PB14_27") (pintype "bidirectional"))
    )
    (net (code "62") (name "unconnected-(U7-PC13-TAMPER-RTC-Pad2)") (class "Default")
      (node (ref "U7") (pin "2") (pinfunction "PC13-TAMPER-RTC_2") (pintype "bidirectional"))
    )
    (net (code "63") (name "unconnected-(U7-PC14-OSC32_IN-Pad3)") (class "Default")
      (node (ref "U7") (pin "3") (pinfunction "PC14-OSC32_IN_3") (pintype "bidirectional"))
    )
    (net (code "64") (name "unconnected-(U7-PC15-OSC32_OUT-Pad4)") (class "Default")
      (node (ref "U7") (pin "4") (pinfunction "PC15-OSC32_OUT_4") (pintype "bidirectional"))
    )
    (net (code "65") (name "unconnected-(U7-VBAT-Pad1)") (class "Default")
      (node (ref "U7") (pin "1") (pinfunction "VBAT_1") (pintype "power_in"))
    )
  )
)
